# DAC.net
KiCad netlist of a schematic drawn in Altium Designer
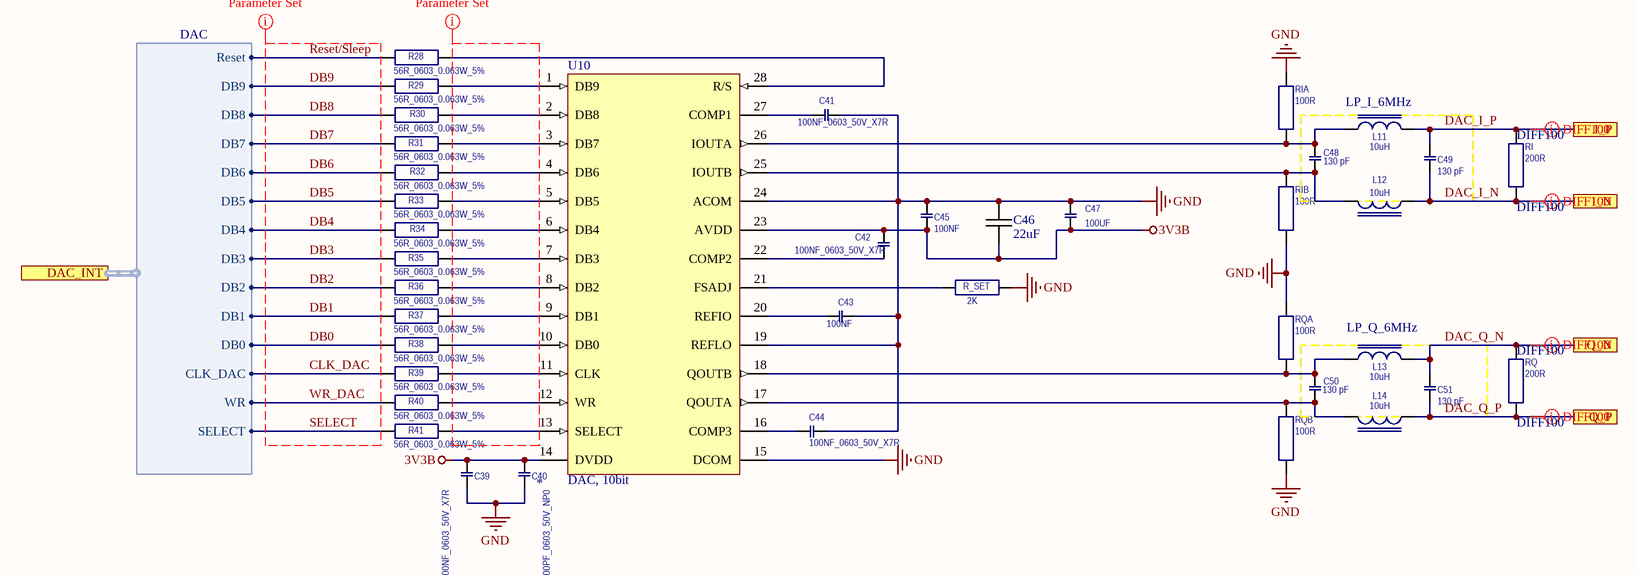
[diagram p0: DAC.SchDoc]

(export (version "E")
  (design (tool "Eeschema 10.0.6"))
  (components
    (comp (ref "C39")
      (value "100NF_0603_50V_X7R")
      (footprint "CAP0603")
      (description "128-8255    Capacitor MLC-X7R_0603_100NF_10%_50V; C0603C104K5RAC; KEMET; RoHS=Yes")
      (libsource (lib "ONEMULA_V2") (part "100NF_0603_50V_X7R"))
    )
    (comp (ref "C40")
      (value "100PF_0603_50V_NP0")
      (footprint "CAP0603")
      (description "141-4603    Capacitor MLC-NPO_0603_100PF_5%_50V; C0603C101J5GAC; KEMET; RoHS=Yes")
      (libsource (lib "ONEMULA_V2") (part "100PF_0603_50V_NP0"))
    )
    (comp (ref "C41")
      (value "100NF_0603_50V_X7R")
      (footprint "CAP0603")
      (description "128-8255    Capacitor MLC-X7R_0603_100NF_10%_50V; C0603C104K5RAC; KEMET; RoHS=Yes")
      (libsource (lib "ONEMULA_V2") (part "100NF_0603_50V_X7R"))
    )
    (comp (ref "C42")
      (value "100NF_0603_50V_X7R")
      (footprint "CAP0603")
      (description "128-8255    Capacitor MLC-X7R_0603_100NF_10%_50V; C0603C104K5RAC; KEMET; RoHS=Yes")
      (libsource (lib "ONEMULA_V2") (part "100NF_0603_50V_X7R"))
    )
    (comp (ref "C43")
      (value "100NF")
      (footprint "CAP0603")
      (description "128-8255    Capacitor MLC-X7R_0603_100NF_10%_50V; C0603C104K5RAC; KEMET; RoHS=Yes")
      (libsource (lib "ONEMULA_V2") (part "100NF_0603_50V_X7R"))
    )
    (comp (ref "C44")
      (value "100NF_0603_50V_X7R")
      (footprint "CAP0603")
      (description "128-8255    Capacitor MLC-X7R_0603_100NF_10%_50V; C0603C104K5RAC; KEMET; RoHS=Yes")
      (libsource (lib "ONEMULA_V2") (part "100NF_0603_50V_X7R"))
    )
    (comp (ref "C45")
      (value "100NF")
      (footprint "CAP0603")
      (description "128-8255    Capacitor MLC-X7R_0603_100NF_10%_50V; C0603C104K5RAC; KEMET; RoHS=Yes")
      (libsource (lib "ONEMULA_V2") (part "100NF_0603_50V_X7R"))
    )
    (comp (ref "C46")
      (value "22uF")
      (footprint "0805C-GENERIC")
      (description "CAPACITOR 0805 CERAMIC")
      (fields (field (name "TOLERANCE") "±20%") (field (name "MANUFACTURER") "TDK Corporation"))
      (libsource (lib "vh_altium_library") (part "0805C-22UF-6V3-X5R-TDK"))
    )
    (comp (ref "C47")
      (value "100UF")
      (footprint "CAP1210")
      (description "182-8817    Capacitor CML 100uF_1210_6.3V_X5R_20%; GRM32ER60J107ME20L; MURATA; RoHS=Yes")
      (libsource (lib "ONEMULA_V2") (part "100UF_1210_6.3V_X5R"))
    )
    (comp (ref "C48")
      (value "130 pF")
      (footprint "CAP0603")
      (description "128-8255    Capacitor MLC-X7R_0603_100NF_10%_50V; C0603C104K5RAC; KEMET; RoHS=Yes")
      (libsource (lib "ONEMULA_V2") (part "100NF_0603_50V_X7R"))
    )
    (comp (ref "C49")
      (value "130 pF")
      (footprint "CAP0603")
      (description "128-8255    Capacitor MLC-X7R_0603_100NF_10%_50V; C0603C104K5RAC; KEMET; RoHS=Yes")
      (libsource (lib "ONEMULA_V2") (part "100NF_0603_50V_X7R"))
    )
    (comp (ref "C50")
      (value "130 pF")
      (footprint "CAP0603")
      (description "128-8255    Capacitor MLC-X7R_0603_100NF_10%_50V; C0603C104K5RAC; KEMET; RoHS=Yes")
      (libsource (lib "ONEMULA_V2") (part "100NF_0603_50V_X7R"))
    )
    (comp (ref "C51")
      (value "130 pF")
      (footprint "CAP0603")
      (description "128-8255    Capacitor MLC-X7R_0603_100NF_10%_50V; C0603C104K5RAC; KEMET; RoHS=Yes")
      (libsource (lib "ONEMULA_V2") (part "100NF_0603_50V_X7R"))
    )
    (comp (ref "L11")
      (value "10uH")
      (footprint "L0805")
      (description "161-1995    FERRITE CHIP BEAD 500mA, 600Ohm@100MHz; BK2125HM601-T; TAIYO YUDEN; RoHS=Yes")
      (libsource (lib "ONEMULA_V2") (part "BK2125HM601-T"))
    )
    (comp (ref "L12")
      (value "10uH")
      (footprint "L0805")
      (description "161-1995    FERRITE CHIP BEAD 500mA, 600Ohm@100MHz; BK2125HM601-T; TAIYO YUDEN; RoHS=Yes")
      (libsource (lib "ONEMULA_V2") (part "BK2125HM601-T"))
    )
    (comp (ref "L13")
      (value "10uH")
      (footprint "L0805")
      (description "161-1995    FERRITE CHIP BEAD 500mA, 600Ohm@100MHz; BK2125HM601-T; TAIYO YUDEN; RoHS=Yes")
      (libsource (lib "ONEMULA_V2") (part "BK2125HM601-T"))
    )
    (comp (ref "L14")
      (value "10uH")
      (footprint "L0805")
      (description "161-1995    FERRITE CHIP BEAD 500mA, 600Ohm@100MHz; BK2125HM601-T; TAIYO YUDEN; RoHS=Yes")
      (libsource (lib "ONEMULA_V2") (part "BK2125HM601-T"))
    )
    (comp (ref "R28")
      (value "56R_0603_0.063W_5%")
      (footprint "R0603")
      (description "923-3130    RESISTOR MF_0603_0.0R_0.1W_50V; RC0603JR-070RL; YAGEO; RoHS=Yes")
      (libsource (lib "ONEMULA_V2") (part "0.0R_0603_0.063W_5%"))
    )
    (comp (ref "R29")
      (value "56R_0603_0.063W_5%")
      (footprint "R0603")
      (description "923-3130    RESISTOR MF_0603_0.0R_0.1W_50V; RC0603JR-070RL; YAGEO; RoHS=Yes")
      (libsource (lib "ONEMULA_V2") (part "0.0R_0603_0.063W_5%"))
    )
    (comp (ref "R30")
      (value "56R_0603_0.063W_5%")
      (footprint "R0603")
      (description "923-3130    RESISTOR MF_0603_0.0R_0.1W_50V; RC0603JR-070RL; YAGEO; RoHS=Yes")
      (libsource (lib "ONEMULA_V2") (part "0.0R_0603_0.063W_5%"))
    )
    (comp (ref "R31")
      (value "56R_0603_0.063W_5%")
      (footprint "R0603")
      (description "923-3130    RESISTOR MF_0603_0.0R_0.1W_50V; RC0603JR-070RL; YAGEO; RoHS=Yes")
      (libsource (lib "ONEMULA_V2") (part "0.0R_0603_0.063W_5%"))
    )
    (comp (ref "R32")
      (value "56R_0603_0.063W_5%")
      (footprint "R0603")
      (description "923-3130    RESISTOR MF_0603_0.0R_0.1W_50V; RC0603JR-070RL; YAGEO; RoHS=Yes")
      (libsource (lib "ONEMULA_V2") (part "0.0R_0603_0.063W_5%"))
    )
    (comp (ref "R33")
      (value "56R_0603_0.063W_5%")
      (footprint "R0603")
      (description "923-3130    RESISTOR MF_0603_0.0R_0.1W_50V; RC0603JR-070RL; YAGEO; RoHS=Yes")
      (libsource (lib "ONEMULA_V2") (part "0.0R_0603_0.063W_5%"))
    )
    (comp (ref "R34")
      (value "56R_0603_0.063W_5%")
      (footprint "R0603")
      (description "923-3130    RESISTOR MF_0603_0.0R_0.1W_50V; RC0603JR-070RL; YAGEO; RoHS=Yes")
      (libsource (lib "ONEMULA_V2") (part "0.0R_0603_0.063W_5%"))
    )
    (comp (ref "R35")
      (value "56R_0603_0.063W_5%")
      (footprint "R0603")
      (description "923-3130    RESISTOR MF_0603_0.0R_0.1W_50V; RC0603JR-070RL; YAGEO; RoHS=Yes")
      (libsource (lib "ONEMULA_V2") (part "0.0R_0603_0.063W_5%"))
    )
    (comp (ref "R36")
      (value "56R_0603_0.063W_5%")
      (footprint "R0603")
      (description "923-3130    RESISTOR MF_0603_0.0R_0.1W_50V; RC0603JR-070RL; YAGEO; RoHS=Yes")
      (libsource (lib "ONEMULA_V2") (part "0.0R_0603_0.063W_5%"))
    )
    (comp (ref "R37")
      (value "56R_0603_0.063W_5%")
      (footprint "R0603")
      (description "923-3130    RESISTOR MF_0603_0.0R_0.1W_50V; RC0603JR-070RL; YAGEO; RoHS=Yes")
      (libsource (lib "ONEMULA_V2") (part "0.0R_0603_0.063W_5%"))
    )
    (comp (ref "R38")
      (value "56R_0603_0.063W_5%")
      (footprint "R0603")
      (description "923-3130    RESISTOR MF_0603_0.0R_0.1W_50V; RC0603JR-070RL; YAGEO; RoHS=Yes")
      (libsource (lib "ONEMULA_V2") (part "0.0R_0603_0.063W_5%"))
    )
    (comp (ref "R39")
      (value "56R_0603_0.063W_5%")
      (footprint "R0603")
      (description "923-3130    RESISTOR MF_0603_0.0R_0.1W_50V; RC0603JR-070RL; YAGEO; RoHS=Yes")
      (libsource (lib "ONEMULA_V2") (part "0.0R_0603_0.063W_5%"))
    )
    (comp (ref "R40")
      (value "56R_0603_0.063W_5%")
      (footprint "R0603")
      (description "923-3130    RESISTOR MF_0603_0.0R_0.1W_50V; RC0603JR-070RL; YAGEO; RoHS=Yes")
      (libsource (lib "ONEMULA_V2") (part "0.0R_0603_0.063W_5%"))
    )
    (comp (ref "R41")
      (value "56R_0603_0.063W_5%")
      (footprint "R0603")
      (description "923-3130    RESISTOR MF_0603_0.0R_0.1W_50V; RC0603JR-070RL; YAGEO; RoHS=Yes")
      (libsource (lib "ONEMULA_V2") (part "0.0R_0603_0.063W_5%"))
    )
    (comp (ref "RI")
      (value "200R")
      (footprint "R0603")
      (description "146-9752    RESISTOR MF_0603_100R_0.1W_1%_75V; CRCW0603100RFKEA; VISHAY; RoHS=Yes")
      (libsource (lib "ONEMULA_V2") (part "100R_0603_0.1W_1%"))
    )
    (comp (ref "RIA")
      (value "100R")
      (footprint "R0603")
      (description "923-3385    RESISTOR MF_0603_1.0KR_0.063W_5%_50V; 232270260102; PHYCOMP; RoHS=Yes")
      (libsource (lib "ONEMULA_V2") (part "1.0K_0603_0.063W_5%"))
    )
    (comp (ref "RIB")
      (value "100R")
      (footprint "R0603")
      (description "923-3385    RESISTOR MF_0603_1.0KR_0.063W_5%_50V; 232270260102; PHYCOMP; RoHS=Yes")
      (libsource (lib "ONEMULA_V2") (part "1.0K_0603_0.063W_5%"))
    )
    (comp (ref "RQ")
      (value "200R")
      (footprint "R0603")
      (description "146-9752    RESISTOR MF_0603_100R_0.1W_1%_75V; CRCW0603100RFKEA; VISHAY; RoHS=Yes")
      (libsource (lib "ONEMULA_V2") (part "100R_0603_0.1W_1%"))
    )
    (comp (ref "RQA")
      (value "100R")
      (footprint "R0603")
      (description "923-3385    RESISTOR MF_0603_1.0KR_0.063W_5%_50V; 232270260102; PHYCOMP; RoHS=Yes")
      (libsource (lib "ONEMULA_V2") (part "1.0K_0603_0.063W_5%"))
    )
    (comp (ref "RQB")
      (value "100R")
      (footprint "R0603")
      (description "923-3385    RESISTOR MF_0603_1.0KR_0.063W_5%_50V; 232270260102; PHYCOMP; RoHS=Yes")
      (libsource (lib "ONEMULA_V2") (part "1.0K_0603_0.063W_5%"))
    )
    (comp (ref "R_SET")
      (value "2K")
      (footprint "R0603")
      (description "146-9765    RESISTOR MF_0603_2K2_0.1W_1%_75V; CRCW06032K20FKEA; VISHAY; RoHS=Yes")
      (libsource (lib "ONEMULA_V2") (part "2K2_0603_0.1W_1%"))
    )
    (comp (ref "U10")
      (value "DAC, 10bit")
      (footprint "SSOP28")
      (fields (field (name "PARAMETER 1") "*"))
      (libsource (lib "My_library") (part "AD9761"))
    )
  )
  (nets
    (net (code "2") (name "/CLK_DAC") (class "Default")
      (node (ref "R39") (pin "1") (pinfunction "1_1") (pintype "passive"))
    )
    (net (code "3") (name "/DAC_I_N") (class "Default")
      (node (ref "C49") (pin "2") (pinfunction "2_2") (pintype "passive"))
      (node (ref "L12") (pin "1") (pinfunction "1_1") (pintype "passive"))
      (node (ref "RI") (pin "1") (pinfunction "1_1") (pintype "passive"))
    )
    (net (code "4") (name "/DAC_I_P") (class "Default")
      (node (ref "C49") (pin "1") (pinfunction "1_1") (pintype "passive"))
      (node (ref "L11") (pin "2") (pinfunction "2_2") (pintype "passive"))
      (node (ref "RI") (pin "2") (pinfunction "2_2") (pintype "passive"))
    )
    (net (code "5") (name "/DAC_Q_N") (class "Default")
      (node (ref "C51") (pin "1") (pinfunction "1_1") (pintype "passive"))
      (node (ref "L13") (pin "2") (pinfunction "2_2") (pintype "passive"))
      (node (ref "RQ") (pin "2") (pinfunction "2_2") (pintype "passive"))
    )
    (net (code "6") (name "/DAC_Q_P") (class "Default")
      (node (ref "C51") (pin "2") (pinfunction "2_2") (pintype "passive"))
      (node (ref "L14") (pin "1") (pinfunction "1_1") (pintype "passive"))
      (node (ref "RQ") (pin "1") (pinfunction "1_1") (pintype "passive"))
    )
    (net (code "7") (name "/DB0") (class "Default")
      (node (ref "R38") (pin "1") (pinfunction "1_1") (pintype "passive"))
    )
    (net (code "8") (name "/DB1") (class "Default")
      (node (ref "R37") (pin "1") (pinfunction "1_1") (pintype "passive"))
    )
    (net (code "9") (name "/DB2") (class "Default")
      (node (ref "R36") (pin "1") (pinfunction "1_1") (pintype "passive"))
    )
    (net (code "10") (name "/DB3") (class "Default")
      (node (ref "R35") (pin "1") (pinfunction "1_1") (pintype "passive"))
    )
    (net (code "11") (name "/DB4") (class "Default")
      (node (ref "R34") (pin "1") (pinfunction "1_1") (pintype "passive"))
    )
    (net (code "12") (name "/DB5") (class "Default")
      (node (ref "R33") (pin "1") (pinfunction "1_1") (pintype "passive"))
    )
    (net (code "13") (name "/DB6") (class "Default")
      (node (ref "R32") (pin "1") (pinfunction "1_1") (pintype "passive"))
    )
    (net (code "14") (name "/DB7") (class "Default")
      (node (ref "R31") (pin "1") (pinfunction "1_1") (pintype "passive"))
    )
    (net (code "15") (name "/DB8") (class "Default")
      (node (ref "R30") (pin "1") (pinfunction "1_1") (pintype "passive"))
    )
    (net (code "16") (name "/DB9") (class "Default")
      (node (ref "R29") (pin "1") (pinfunction "1_1") (pintype "passive"))
    )
    (net (code "17") (name "/Reset{slash}Sleep") (class "Default")
      (node (ref "R28") (pin "1") (pinfunction "1_1") (pintype "passive"))
    )
    (net (code "18") (name "/SELECT") (class "Default")
      (node (ref "R41") (pin "1") (pinfunction "1_1") (pintype "passive"))
    )
    (net (code "19") (name "/WR_DAC") (class "Default")
      (node (ref "R40") (pin "1") (pinfunction "1_1") (pintype "passive"))
    )
    (net (code "21") (name "3V3B") (class "Default")
      (node (ref "C39") (pin "1") (pinfunction "1_1") (pintype "passive"))
      (node (ref "C40") (pin "1") (pinfunction "1_1") (pintype "passive"))
      (node (ref "C42") (pin "2") (pinfunction "2_2") (pintype "passive"))
      (node (ref "C45") (pin "2") (pinfunction "2_2") (pintype "passive"))
      (node (ref "C46") (pin "2") (pintype "passive"))
      (node (ref "C47") (pin "2") (pinfunction "2_2") (pintype "passive"))
      (node (ref "U10") (pin "14") (pinfunction "DVDD_14") (pintype "power_in"))
      (node (ref "U10") (pin "23") (pinfunction "AVDD_23") (pintype "passive"))
    )
    (net (code "22") (name "GND") (class "Default")
      (node (ref "C39") (pin "2") (pinfunction "2_2") (pintype "passive"))
      (node (ref "C40") (pin "2") (pinfunction "2_2") (pintype "passive"))
      (node (ref "C41") (pin "2") (pinfunction "2_2") (pintype "passive"))
      (node (ref "C43") (pin "2") (pinfunction "2_2") (pintype "passive"))
      (node (ref "C44") (pin "1") (pinfunction "1_1") (pintype "passive"))
      (node (ref "C45") (pin "1") (pinfunction "1_1") (pintype "passive"))
      (node (ref "C46") (pin "1") (pintype "passive"))
      (node (ref "C47") (pin "1") (pinfunction "1_1") (pintype "passive"))
      (node (ref "RIA") (pin "2") (pinfunction "2_2") (pintype "passive"))
      (node (ref "RIB") (pin "1") (pinfunction "1_1") (pintype "passive"))
      (node (ref "RQA") (pin "2") (pinfunction "2_2") (pintype "passive"))
      (node (ref "RQB") (pin "1") (pinfunction "1_1") (pintype "passive"))
      (node (ref "R_SET") (pin "2") (pinfunction "2_2") (pintype "passive"))
      (node (ref "U10") (pin "15") (pinfunction "DCOM_15") (pintype "passive"))
      (node (ref "U10") (pin "19") (pinfunction "REFLO_19") (pintype "passive"))
      (node (ref "U10") (pin "24") (pinfunction "ACOM_24") (pintype "passive"))
    )
    (net (code "23") (name "Net-(U10-CLK)") (class "Default")
      (node (ref "R39") (pin "2") (pinfunction "2_2") (pintype "passive"))
      (node (ref "U10") (pin "11") (pinfunction "CLK_11") (pintype "input"))
    )
    (net (code "24") (name "Net-(U10-COMP1)") (class "Default")
      (node (ref "C41") (pin "1") (pinfunction "1_1") (pintype "passive"))
      (node (ref "U10") (pin "27") (pinfunction "COMP1_27") (pintype "passive"))
    )
    (net (code "25") (name "Net-(U10-COMP2)") (class "Default")
      (node (ref "C42") (pin "1") (pinfunction "1_1") (pintype "passive"))
      (node (ref "U10") (pin "22") (pinfunction "COMP2_22") (pintype "passive"))
    )
    (net (code "26") (name "Net-(U10-COMP3)") (class "Default")
      (node (ref "C44") (pin "2") (pinfunction "2_2") (pintype "passive"))
      (node (ref "U10") (pin "16") (pinfunction "COMP3_16") (pintype "passive"))
    )
    (net (code "27") (name "Net-(U10-DB0)") (class "Default")
      (node (ref "R38") (pin "2") (pinfunction "2_2") (pintype "passive"))
      (node (ref "U10") (pin "10") (pinfunction "DB0_10") (pintype "input"))
    )
    (net (code "28") (name "Net-(U10-DB1)") (class "Default")
      (node (ref "R37") (pin "2") (pinfunction "2_2") (pintype "passive"))
      (node (ref "U10") (pin "9") (pinfunction "DB1_9") (pintype "input"))
    )
    (net (code "29") (name "Net-(U10-DB2)") (class "Default")
      (node (ref "R36") (pin "2") (pinfunction "2_2") (pintype "passive"))
      (node (ref "U10") (pin "8") (pinfunction "DB2_8") (pintype "input"))
    )
    (net (code "30") (name "Net-(U10-DB3)") (class "Default")
      (node (ref "R35") (pin "2") (pinfunction "2_2") (pintype "passive"))
      (node (ref "U10") (pin "7") (pinfunction "DB3_7") (pintype "input"))
    )
    (net (code "31") (name "Net-(U10-DB4)") (class "Default")
      (node (ref "R34") (pin "2") (pinfunction "2_2") (pintype "passive"))
      (node (ref "U10") (pin "6") (pinfunction "DB4_6") (pintype "input"))
    )
    (net (code "32") (name "Net-(U10-DB5)") (class "Default")
      (node (ref "R33") (pin "2") (pinfunction "2_2") (pintype "passive"))
      (node (ref "U10") (pin "5") (pinfunction "DB5_5") (pintype "input"))
    )
    (net (code "33") (name "Net-(U10-DB6)") (class "Default")
      (node (ref "R32") (pin "2") (pinfunction "2_2") (pintype "passive"))
      (node (ref "U10") (pin "4") (pinfunction "DB6_4") (pintype "input"))
    )
    (net (code "34") (name "Net-(U10-DB7)") (class "Default")
      (node (ref "R31") (pin "2") (pinfunction "2_2") (pintype "passive"))
      (node (ref "U10") (pin "3") (pinfunction "DB7_3") (pintype "input"))
    )
    (net (code "35") (name "Net-(U10-DB8)") (class "Default")
      (node (ref "R30") (pin "2") (pinfunction "2_2") (pintype "passive"))
      (node (ref "U10") (pin "2") (pinfunction "DB8_2") (pintype "input"))
    )
    (net (code "36") (name "Net-(U10-DB9)") (class "Default")
      (node (ref "R29") (pin "2") (pinfunction "2_2") (pintype "passive"))
      (node (ref "U10") (pin "1") (pinfunction "DB9_1") (pintype "input"))
    )
    (net (code "37") (name "Net-(U10-FSADJ)") (class "Default")
      (node (ref "R_SET") (pin "1") (pinfunction "1_1") (pintype "passive"))
      (node (ref "U10") (pin "21") (pinfunction "FSADJ_21") (pintype "passive"))
    )
    (net (code "38") (name "Net-(U10-IOUTA)") (class "Default")
      (node (ref "C48") (pin "1") (pinfunction "1_1") (pintype "passive"))
      (node (ref "L11") (pin "1") (pinfunction "1_1") (pintype "passive"))
      (node (ref "RIA") (pin "1") (pinfunction "1_1") (pintype "passive"))
      (node (ref "U10") (pin "26") (pinfunction "IOUTA_26") (pintype "output"))
    )
    (net (code "39") (name "Net-(U10-IOUTB)") (class "Default")
      (node (ref "C48") (pin "2") (pinfunction "2_2") (pintype "passive"))
      (node (ref "L12") (pin "2") (pinfunction "2_2") (pintype "passive"))
      (node (ref "RIB") (pin "2") (pinfunction "2_2") (pintype "passive"))
      (node (ref "U10") (pin "25") (pinfunction "IOUTB_25") (pintype "output"))
    )
    (net (code "40") (name "Net-(U10-QOUTA)") (class "Default")
      (node (ref "C50") (pin "2") (pinfunction "2_2") (pintype "passive"))
      (node (ref "L14") (pin "2") (pinfunction "2_2") (pintype "passive"))
      (node (ref "RQB") (pin "2") (pinfunction "2_2") (pintype "passive"))
      (node (ref "U10") (pin "17") (pinfunction "QOUTA_17") (pintype "output"))
    )
    (net (code "41") (name "Net-(U10-QOUTB)") (class "Default")
      (node (ref "C50") (pin "1") (pinfunction "1_1") (pintype "passive"))
      (node (ref "L13") (pin "1") (pinfunction "1_1") (pintype "passive"))
      (node (ref "RQA") (pin "1") (pinfunction "1_1") (pintype "passive"))
      (node (ref "U10") (pin "18") (pinfunction "QOUTB_18") (pintype "output"))
    )
    (net (code "42") (name "Net-(U10-REFIO)") (class "Default")
      (node (ref "C43") (pin "1") (pinfunction "1_1") (pintype "passive"))
      (node (ref "U10") (pin "20") (pinfunction "REFIO_20") (pintype "passive"))
    )
    (net (code "43") (name "Net-(U10-R{slash}S)") (class "Default")
      (node (ref "R28") (pin "2") (pinfunction "2_2") (pintype "passive"))
      (node (ref "U10") (pin "28") (pinfunction "R/S_28") (pintype "input"))
    )
    (net (code "44") (name "Net-(U10-SELECT)") (class "Default")
      (node (ref "R41") (pin "2") (pinfunction "2_2") (pintype "passive"))
      (node (ref "U10") (pin "13") (pinfunction "SELECT_13") (pintype "input"))
    )
    (net (code "45") (name "Net-(U10-WR)") (class "Default")
      (node (ref "R40") (pin "2") (pinfunction "2_2") (pintype "passive"))
      (node (ref "U10") (pin "12") (pinfunction "WR_12") (pintype "input"))
    )
  )
)
